# Relay_outputs1_double.net
KiCad netlist of a schematic drawn in EAGLE
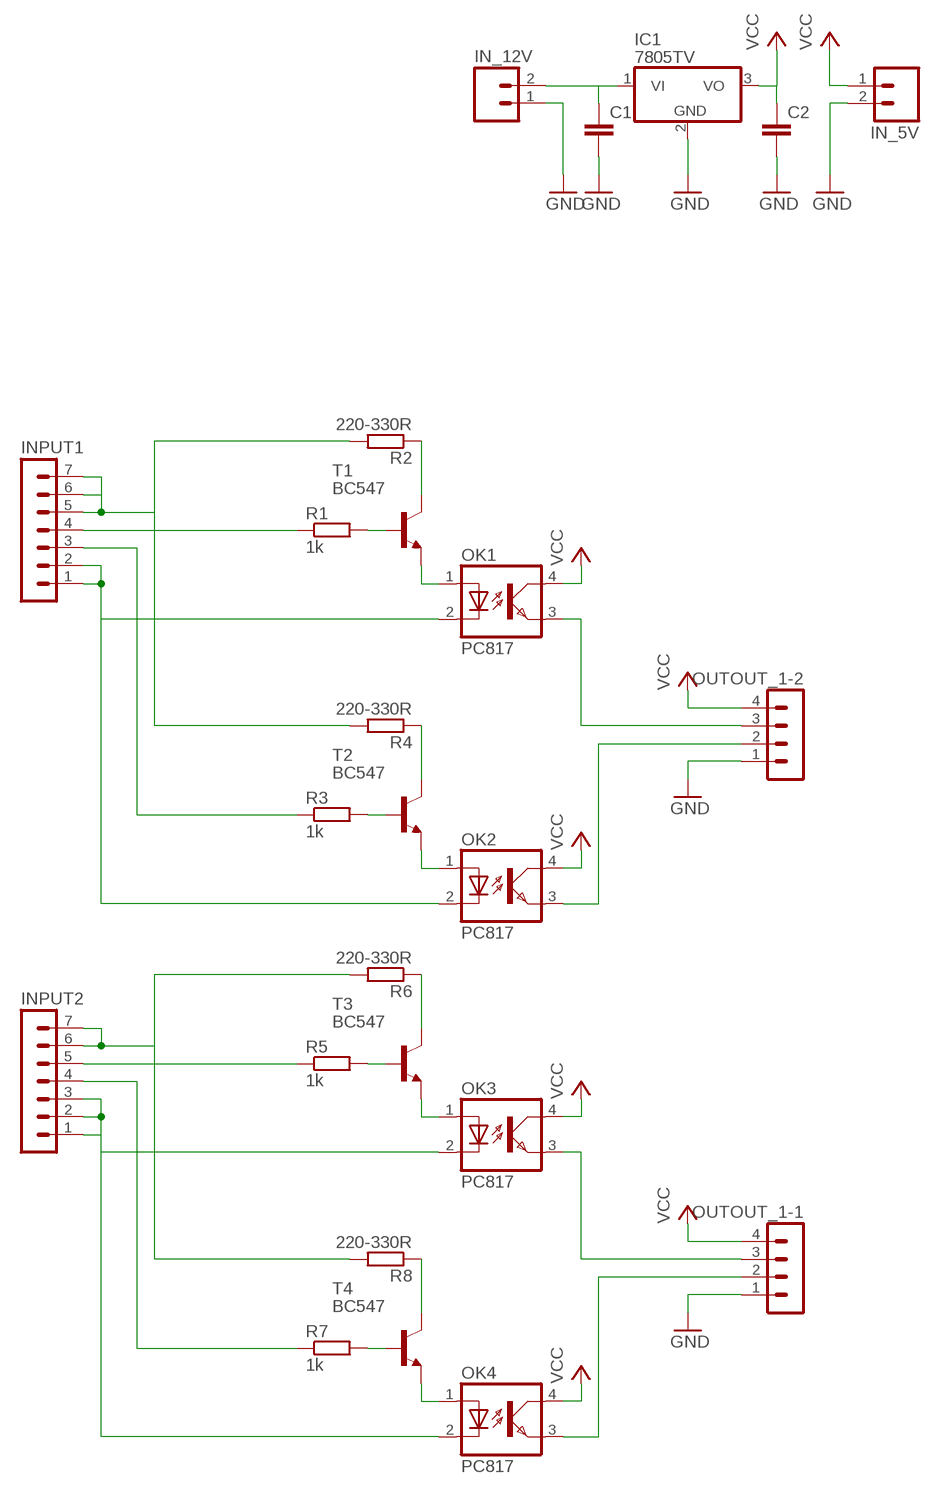
[diagram p0: schematic, sheet 1]

(export (version "E")
  (design (tool "Eeschema 10.0.6"))
  (components
    (comp (ref "C1")
      (value "C-EU050-024X044")
      (footprint "eagle-import:C050-024X044")
      (libsource (lib "eagle-import") (part "C-EU050-024X044"))
    )
    (comp (ref "C2")
      (value "C-EU050-024X044")
      (footprint "eagle-import:C050-024X044")
      (libsource (lib "eagle-import") (part "C-EU050-024X044"))
    )
    (comp (ref "IC1")
      (value "7805TV")
      (footprint "eagle-import:TO220V")
      (libsource (lib "eagle-import") (part "78TV05"))
    )
    (comp (ref "INPUT1")
      (value "MA07-1")
      (footprint "eagle-import:MA07-1")
      (libsource (lib "eagle-import") (part "MA07-1"))
    )
    (comp (ref "INPUT2")
      (value "MA07-1")
      (footprint "eagle-import:MA07-1")
      (libsource (lib "eagle-import") (part "MA07-1"))
    )
    (comp (ref "IN_5V")
      (value "MA02")
      (footprint "eagle-import:02PA")
      (libsource (lib "eagle-import") (part "MA02"))
    )
    (comp (ref "IN_12V")
      (value "MA02")
      (footprint "eagle-import:02PA")
      (libsource (lib "eagle-import") (part "MA02"))
    )
    (comp (ref "OK1")
      (value "PC817")
      (footprint "eagle-import:DIL04")
      (libsource (lib "eagle-import") (part "PC817"))
    )
    (comp (ref "OK2")
      (value "PC817")
      (footprint "eagle-import:DIL04")
      (libsource (lib "eagle-import") (part "PC817"))
    )
    (comp (ref "OK3")
      (value "PC817")
      (footprint "eagle-import:DIL04")
      (libsource (lib "eagle-import") (part "PC817"))
    )
    (comp (ref "OK4")
      (value "PC817")
      (footprint "eagle-import:DIL04")
      (libsource (lib "eagle-import") (part "PC817"))
    )
    (comp (ref "OUTOUT_1-1")
      (value "MA04-1")
      (footprint "eagle-import:MA04-1")
      (libsource (lib "eagle-import") (part "MA04-1"))
    )
    (comp (ref "OUTOUT_1-2")
      (value "MA04-1")
      (footprint "eagle-import:MA04-1")
      (libsource (lib "eagle-import") (part "MA04-1"))
    )
    (comp (ref "R1")
      (value "1k")
      (footprint "eagle-import:0207_10")
      (libsource (lib "eagle-import") (part "R-EU_0207/10"))
    )
    (comp (ref "R2")
      (value "220-330R")
      (footprint "eagle-import:0207_10")
      (libsource (lib "eagle-import") (part "R-EU_0207/10"))
    )
    (comp (ref "R3")
      (value "1k")
      (footprint "eagle-import:0207_10")
      (libsource (lib "eagle-import") (part "R-EU_0207/10"))
    )
    (comp (ref "R4")
      (value "220-330R")
      (footprint "eagle-import:0207_10")
      (libsource (lib "eagle-import") (part "R-EU_0207/10"))
    )
    (comp (ref "R5")
      (value "1k")
      (footprint "eagle-import:0207_10")
      (libsource (lib "eagle-import") (part "R-EU_0207/10"))
    )
    (comp (ref "R6")
      (value "220-330R")
      (footprint "eagle-import:0207_10")
      (libsource (lib "eagle-import") (part "R-EU_0207/10"))
    )
    (comp (ref "R7")
      (value "1k")
      (footprint "eagle-import:0207_10")
      (libsource (lib "eagle-import") (part "R-EU_0207/10"))
    )
    (comp (ref "R8")
      (value "220-330R")
      (footprint "eagle-import:0207_10")
      (libsource (lib "eagle-import") (part "R-EU_0207/10"))
    )
    (comp (ref "T1")
      (value "BC547")
      (footprint "eagle-import:TO92")
      (libsource (lib "eagle-import") (part "BC547"))
    )
    (comp (ref "T2")
      (value "BC547")
      (footprint "eagle-import:TO92")
      (libsource (lib "eagle-import") (part "BC547"))
    )
    (comp (ref "T3")
      (value "BC547")
      (footprint "eagle-import:TO92")
      (libsource (lib "eagle-import") (part "BC547"))
    )
    (comp (ref "T4")
      (value "BC547")
      (footprint "eagle-import:TO92")
      (libsource (lib "eagle-import") (part "BC547"))
    )
  )
  (nets
    (net (code "1") (name "GND") (class "Default")
      (node (ref "C1") (pin "2") (pinfunction "2_2") (pintype "passive"))
      (node (ref "C2") (pin "2") (pinfunction "2_2") (pintype "passive"))
      (node (ref "IC1") (pin "2") (pinfunction "GND_2") (pintype "passive"))
      (node (ref "IN_12V") (pin "1") (pinfunction "1_1") (pintype "passive"))
      (node (ref "IN_5V") (pin "2") (pinfunction "2_2") (pintype "passive"))
      (node (ref "OUTOUT_1-1") (pin "1") (pinfunction "1_1") (pintype "passive"))
      (node (ref "OUTOUT_1-2") (pin "1") (pinfunction "1_1") (pintype "passive"))
    )
    (net (code "2") (name "Net-(IC1-VI)") (class "Default")
      (node (ref "C1") (pin "1") (pinfunction "1_1") (pintype "passive"))
      (node (ref "IC1") (pin "1") (pinfunction "VI_1") (pintype "input"))
      (node (ref "IN_12V") (pin "2") (pinfunction "2_2") (pintype "passive"))
    )
    (net (code "3") (name "Net-(INPUT1-Pad3)") (class "Default")
      (node (ref "INPUT1") (pin "3") (pinfunction "3_3") (pintype "passive"))
      (node (ref "R3") (pin "1") (pinfunction "1_1") (pintype "passive"))
    )
    (net (code "4") (name "Net-(INPUT1-Pad4)") (class "Default")
      (node (ref "INPUT1") (pin "4") (pinfunction "4_4") (pintype "passive"))
      (node (ref "R1") (pin "1") (pinfunction "1_1") (pintype "passive"))
    )
    (net (code "5") (name "Net-(INPUT1-Pad5)") (class "Default")
      (node (ref "INPUT1") (pin "5") (pinfunction "5_5") (pintype "passive"))
      (node (ref "INPUT1") (pin "6") (pinfunction "6_6") (pintype "passive"))
      (node (ref "INPUT1") (pin "7") (pinfunction "7_7") (pintype "passive"))
      (node (ref "R2") (pin "2") (pinfunction "2_2") (pintype "passive"))
      (node (ref "R4") (pin "2") (pinfunction "2_2") (pintype "passive"))
    )
    (net (code "6") (name "Net-(INPUT2-Pad4)") (class "Default")
      (node (ref "INPUT2") (pin "4") (pinfunction "4_4") (pintype "passive"))
      (node (ref "R7") (pin "1") (pinfunction "1_1") (pintype "passive"))
    )
    (net (code "7") (name "Net-(INPUT2-Pad5)") (class "Default")
      (node (ref "INPUT2") (pin "5") (pinfunction "5_5") (pintype "passive"))
      (node (ref "R5") (pin "1") (pinfunction "1_1") (pintype "passive"))
    )
    (net (code "8") (name "Net-(INPUT2-Pad6)") (class "Default")
      (node (ref "INPUT2") (pin "6") (pinfunction "6_6") (pintype "passive"))
      (node (ref "INPUT2") (pin "7") (pinfunction "7_7") (pintype "passive"))
      (node (ref "R6") (pin "2") (pinfunction "2_2") (pintype "passive"))
      (node (ref "R8") (pin "2") (pinfunction "2_2") (pintype "passive"))
    )
    (net (code "9") (name "Net-(OK1-A)") (class "Default")
      (node (ref "OK1") (pin "1") (pinfunction "A_1") (pintype "passive"))
      (node (ref "T1") (pin "1") (pinfunction "E_1") (pintype "passive"))
    )
    (net (code "10") (name "Net-(OK1-C)") (class "Default")
      (node (ref "INPUT1") (pin "1") (pinfunction "1_1") (pintype "passive"))
      (node (ref "INPUT1") (pin "2") (pinfunction "2_2") (pintype "passive"))
      (node (ref "OK1") (pin "2") (pinfunction "C_2") (pintype "passive"))
      (node (ref "OK2") (pin "2") (pinfunction "C_2") (pintype "passive"))
    )
    (net (code "11") (name "Net-(OK1-EMIT)") (class "Default")
      (node (ref "OK1") (pin "3") (pinfunction "EMIT_3") (pintype "passive"))
      (node (ref "OUTOUT_1-2") (pin "3") (pinfunction "3_3") (pintype "passive"))
    )
    (net (code "12") (name "Net-(OK2-A)") (class "Default")
      (node (ref "OK2") (pin "1") (pinfunction "A_1") (pintype "passive"))
      (node (ref "T2") (pin "1") (pinfunction "E_1") (pintype "passive"))
    )
    (net (code "13") (name "Net-(OK2-EMIT)") (class "Default")
      (node (ref "OK2") (pin "3") (pinfunction "EMIT_3") (pintype "passive"))
      (node (ref "OUTOUT_1-2") (pin "2") (pinfunction "2_2") (pintype "passive"))
    )
    (net (code "14") (name "Net-(OK3-A)") (class "Default")
      (node (ref "OK3") (pin "1") (pinfunction "A_1") (pintype "passive"))
      (node (ref "T3") (pin "1") (pinfunction "E_1") (pintype "passive"))
    )
    (net (code "15") (name "Net-(OK3-C)") (class "Default")
      (node (ref "INPUT2") (pin "1") (pinfunction "1_1") (pintype "passive"))
      (node (ref "INPUT2") (pin "2") (pinfunction "2_2") (pintype "passive"))
      (node (ref "INPUT2") (pin "3") (pinfunction "3_3") (pintype "passive"))
      (node (ref "OK3") (pin "2") (pinfunction "C_2") (pintype "passive"))
      (node (ref "OK4") (pin "2") (pinfunction "C_2") (pintype "passive"))
    )
    (net (code "16") (name "Net-(OK3-EMIT)") (class "Default")
      (node (ref "OK3") (pin "3") (pinfunction "EMIT_3") (pintype "passive"))
      (node (ref "OUTOUT_1-1") (pin "3") (pinfunction "3_3") (pintype "passive"))
    )
    (net (code "17") (name "Net-(OK4-A)") (class "Default")
      (node (ref "OK4") (pin "1") (pinfunction "A_1") (pintype "passive"))
      (node (ref "T4") (pin "1") (pinfunction "E_1") (pintype "passive"))
    )
    (net (code "18") (name "Net-(OK4-EMIT)") (class "Default")
      (node (ref "OK4") (pin "3") (pinfunction "EMIT_3") (pintype "passive"))
      (node (ref "OUTOUT_1-1") (pin "2") (pinfunction "2_2") (pintype "passive"))
    )
    (net (code "19") (name "Net-(T1-B)") (class "Default")
      (node (ref "R1") (pin "2") (pinfunction "2_2") (pintype "passive"))
      (node (ref "T1") (pin "2") (pinfunction "B_2") (pintype "passive"))
    )
    (net (code "20") (name "Net-(T1-C)") (class "Default")
      (node (ref "R2") (pin "1") (pinfunction "1_1") (pintype "passive"))
      (node (ref "T1") (pin "3") (pinfunction "C_3") (pintype "passive"))
    )
    (net (code "21") (name "Net-(T2-B)") (class "Default")
      (node (ref "R3") (pin "2") (pinfunction "2_2") (pintype "passive"))
      (node (ref "T2") (pin "2") (pinfunction "B_2") (pintype "passive"))
    )
    (net (code "22") (name "Net-(T2-C)") (class "Default")
      (node (ref "R4") (pin "1") (pinfunction "1_1") (pintype "passive"))
      (node (ref "T2") (pin "3") (pinfunction "C_3") (pintype "passive"))
    )
    (net (code "23") (name "Net-(T3-B)") (class "Default")
      (node (ref "R5") (pin "2") (pinfunction "2_2") (pintype "passive"))
      (node (ref "T3") (pin "2") (pinfunction "B_2") (pintype "passive"))
    )
    (net (code "24") (name "Net-(T3-C)") (class "Default")
      (node (ref "R6") (pin "1") (pinfunction "1_1") (pintype "passive"))
      (node (ref "T3") (pin "3") (pinfunction "C_3") (pintype "passive"))
    )
    (net (code "25") (name "Net-(T4-B)") (class "Default")
      (node (ref "R7") (pin "2") (pinfunction "2_2") (pintype "passive"))
      (node (ref "T4") (pin "2") (pinfunction "B_2") (pintype "passive"))
    )
    (net (code "26") (name "Net-(T4-C)") (class "Default")
      (node (ref "R8") (pin "1") (pinfunction "1_1") (pintype "passive"))
      (node (ref "T4") (pin "3") (pinfunction "C_3") (pintype "passive"))
    )
    (net (code "27") (name "VCC") (class "Default")
      (node (ref "C2") (pin "1") (pinfunction "1_1") (pintype "passive"))
      (node (ref "IC1") (pin "3") (pinfunction "VO_3") (pintype "passive"))
      (node (ref "IN_5V") (pin "1") (pinfunction "1_1") (pintype "passive"))
      (node (ref "OK1") (pin "4") (pinfunction "COL_4") (pintype "passive"))
      (node (ref "OK2") (pin "4") (pinfunction "COL_4") (pintype "passive"))
      (node (ref "OK3") (pin "4") (pinfunction "COL_4") (pintype "passive"))
      (node (ref "OK4") (pin "4") (pinfunction "COL_4") (pintype "passive"))
      (node (ref "OUTOUT_1-1") (pin "4") (pinfunction "4_4") (pintype "passive"))
      (node (ref "OUTOUT_1-2") (pin "4") (pinfunction "4_4") (pintype "passive"))
    )
  )
)
